# 03_Keys.net
KiCad netlist of a schematic drawn in Altium Designer
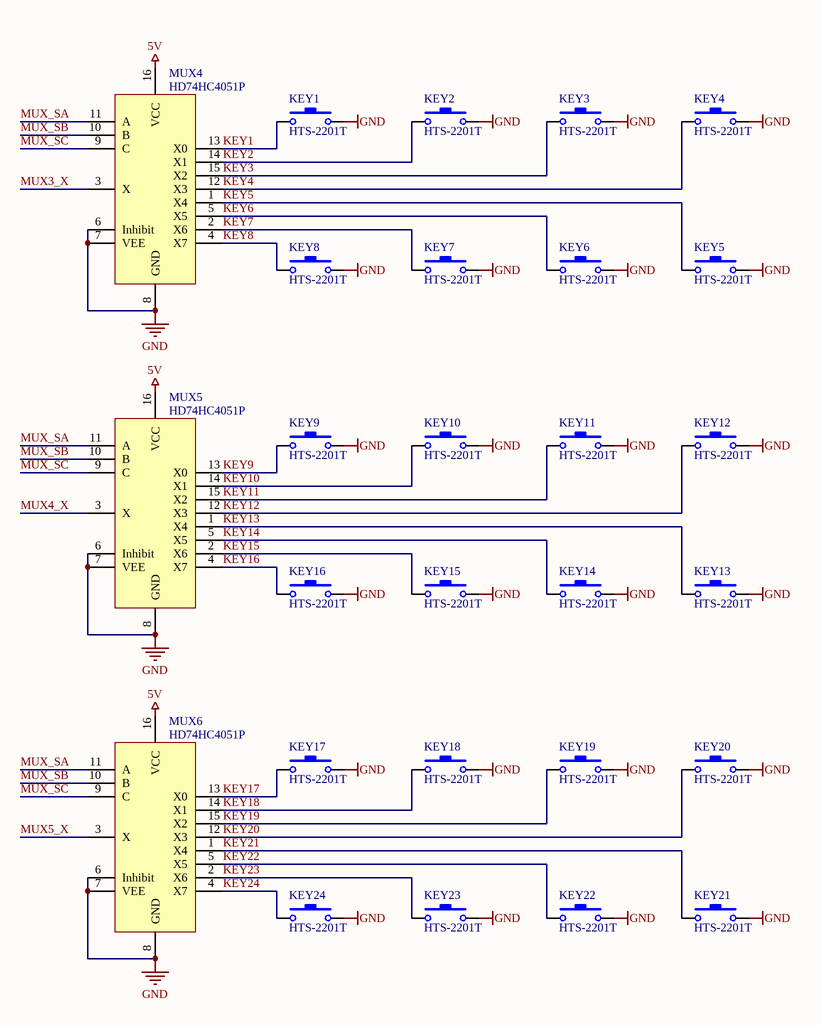
[diagram p0: 03.Keys.SchDoc]

(export (version "E")
  (design (tool "Eeschema 10.0.6"))
  (components
    (comp (ref "KEY1")
      (value "HTS-2201T")
      (footprint "ALPS-SKHC-12mm - NO SILK")
      (libsource (lib "Jixuan's library") (part "Tact Switch HTS-2201T"))
    )
    (comp (ref "KEY2")
      (value "HTS-2201T")
      (footprint "ALPS-SKHC-12mm - NO SILK")
      (libsource (lib "Jixuan's library") (part "Tact Switch HTS-2201T"))
    )
    (comp (ref "KEY3")
      (value "HTS-2201T")
      (footprint "ALPS-SKHC-12mm - NO SILK")
      (libsource (lib "Jixuan's library") (part "Tact Switch HTS-2201T"))
    )
    (comp (ref "KEY4")
      (value "HTS-2201T")
      (footprint "ALPS-SKHC-12mm - NO SILK")
      (libsource (lib "Jixuan's library") (part "Tact Switch HTS-2201T"))
    )
    (comp (ref "KEY5")
      (value "HTS-2201T")
      (footprint "ALPS-SKHC-12mm - NO SILK")
      (libsource (lib "Jixuan's library") (part "Tact Switch HTS-2201T"))
    )
    (comp (ref "KEY6")
      (value "HTS-2201T")
      (footprint "ALPS-SKHC-12mm - NO SILK")
      (libsource (lib "Jixuan's library") (part "Tact Switch HTS-2201T"))
    )
    (comp (ref "KEY7")
      (value "HTS-2201T")
      (footprint "ALPS-SKHC-12mm - NO SILK")
      (libsource (lib "Jixuan's library") (part "Tact Switch HTS-2201T"))
    )
    (comp (ref "KEY8")
      (value "HTS-2201T")
      (footprint "ALPS-SKHC-12mm - NO SILK")
      (libsource (lib "Jixuan's library") (part "Tact Switch HTS-2201T"))
    )
    (comp (ref "KEY9")
      (value "HTS-2201T")
      (footprint "ALPS-SKHC-12mm - NO SILK")
      (libsource (lib "Jixuan's library") (part "Tact Switch HTS-2201T"))
    )
    (comp (ref "KEY10")
      (value "HTS-2201T")
      (footprint "ALPS-SKHC-12mm - NO SILK")
      (libsource (lib "Jixuan's library") (part "Tact Switch HTS-2201T"))
    )
    (comp (ref "KEY11")
      (value "HTS-2201T")
      (footprint "ALPS-SKHC-12mm - NO SILK")
      (libsource (lib "Jixuan's library") (part "Tact Switch HTS-2201T"))
    )
    (comp (ref "KEY12")
      (value "HTS-2201T")
      (footprint "ALPS-SKHC-12mm - NO SILK")
      (libsource (lib "Jixuan's library") (part "Tact Switch HTS-2201T"))
    )
    (comp (ref "KEY13")
      (value "HTS-2201T")
      (footprint "ALPS-SKHC-12mm - NO SILK")
      (libsource (lib "Jixuan's library") (part "Tact Switch HTS-2201T"))
    )
    (comp (ref "KEY14")
      (value "HTS-2201T")
      (footprint "ALPS-SKHC-12mm - NO SILK")
      (libsource (lib "Jixuan's library") (part "Tact Switch HTS-2201T"))
    )
    (comp (ref "KEY15")
      (value "HTS-2201T")
      (footprint "ALPS-SKHC-12mm - NO SILK")
      (libsource (lib "Jixuan's library") (part "Tact Switch HTS-2201T"))
    )
    (comp (ref "KEY16")
      (value "HTS-2201T")
      (footprint "ALPS-SKHC-12mm - NO SILK")
      (libsource (lib "Jixuan's library") (part "Tact Switch HTS-2201T"))
    )
    (comp (ref "KEY17")
      (value "HTS-2201T")
      (footprint "ALPS-SKHC-12mm - NO SILK")
      (libsource (lib "Jixuan's library") (part "Tact Switch HTS-2201T"))
    )
    (comp (ref "KEY18")
      (value "HTS-2201T")
      (footprint "ALPS-SKHC-12mm - NO SILK")
      (libsource (lib "Jixuan's library") (part "Tact Switch HTS-2201T"))
    )
    (comp (ref "KEY19")
      (value "HTS-2201T")
      (footprint "ALPS-SKHC-12mm - NO SILK")
      (libsource (lib "Jixuan's library") (part "Tact Switch HTS-2201T"))
    )
    (comp (ref "KEY20")
      (value "HTS-2201T")
      (footprint "ALPS-SKHC-12mm - NO SILK")
      (libsource (lib "Jixuan's library") (part "Tact Switch HTS-2201T"))
    )
    (comp (ref "KEY21")
      (value "HTS-2201T")
      (footprint "ALPS-SKHC-12mm - NO SILK")
      (libsource (lib "Jixuan's library") (part "Tact Switch HTS-2201T"))
    )
    (comp (ref "KEY22")
      (value "HTS-2201T")
      (footprint "ALPS-SKHC-12mm - NO SILK")
      (libsource (lib "Jixuan's library") (part "Tact Switch HTS-2201T"))
    )
    (comp (ref "KEY23")
      (value "HTS-2201T")
      (footprint "ALPS-SKHC-12mm - NO SILK")
      (libsource (lib "Jixuan's library") (part "Tact Switch HTS-2201T"))
    )
    (comp (ref "KEY24")
      (value "HTS-2201T")
      (footprint "ALPS-SKHC-12mm - NO SILK")
      (libsource (lib "Jixuan's library") (part "Tact Switch HTS-2201T"))
    )
    (comp (ref "MUX4")
      (value "HD74HC4051P")
      (footprint "DIP-16")
      (libsource (lib "Jixuan's library") (part "TC74HC4051AF"))
    )
    (comp (ref "MUX5")
      (value "HD74HC4051P")
      (footprint "DIP-16")
      (libsource (lib "Jixuan's library") (part "TC74HC4051AF"))
    )
    (comp (ref "MUX6")
      (value "HD74HC4051P")
      (footprint "DIP-16")
      (libsource (lib "Jixuan's library") (part "TC74HC4051AF"))
    )
  )
  (nets
    (net (code "1") (name "/KEY1") (class "Default")
      (node (ref "KEY1") (pin "2") (pinfunction "2_2") (pintype "passive"))
      (node (ref "MUX4") (pin "13") (pinfunction "X0_13") (pintype "passive"))
    )
    (net (code "2") (name "/KEY2") (class "Default")
      (node (ref "KEY2") (pin "2") (pinfunction "2_2") (pintype "passive"))
      (node (ref "MUX4") (pin "14") (pinfunction "X1_14") (pintype "passive"))
    )
    (net (code "3") (name "/KEY3") (class "Default")
      (node (ref "KEY3") (pin "2") (pinfunction "2_2") (pintype "passive"))
      (node (ref "MUX4") (pin "15") (pinfunction "X2_15") (pintype "passive"))
    )
    (net (code "4") (name "/KEY4") (class "Default")
      (node (ref "KEY4") (pin "2") (pinfunction "2_2") (pintype "passive"))
      (node (ref "MUX4") (pin "12") (pinfunction "X3_12") (pintype "passive"))
    )
    (net (code "5") (name "/KEY5") (class "Default")
      (node (ref "KEY5") (pin "2") (pinfunction "2_2") (pintype "passive"))
      (node (ref "MUX4") (pin "1") (pinfunction "X4_1") (pintype "passive"))
    )
    (net (code "6") (name "/KEY6") (class "Default")
      (node (ref "KEY6") (pin "2") (pinfunction "2_2") (pintype "passive"))
      (node (ref "MUX4") (pin "5") (pinfunction "X5_5") (pintype "passive"))
    )
    (net (code "7") (name "/KEY7") (class "Default")
      (node (ref "KEY7") (pin "2") (pinfunction "2_2") (pintype "passive"))
      (node (ref "MUX4") (pin "2") (pinfunction "X6_2") (pintype "passive"))
    )
    (net (code "8") (name "/KEY8") (class "Default")
      (node (ref "KEY8") (pin "2") (pinfunction "2_2") (pintype "passive"))
      (node (ref "MUX4") (pin "4") (pinfunction "X7_4") (pintype "passive"))
    )
    (net (code "9") (name "/KEY9") (class "Default")
      (node (ref "KEY9") (pin "2") (pinfunction "2_2") (pintype "passive"))
      (node (ref "MUX5") (pin "13") (pinfunction "X0_13") (pintype "passive"))
    )
    (net (code "10") (name "/KEY10") (class "Default")
      (node (ref "KEY10") (pin "2") (pinfunction "2_2") (pintype "passive"))
      (node (ref "MUX5") (pin "14") (pinfunction "X1_14") (pintype "passive"))
    )
    (net (code "11") (name "/KEY11") (class "Default")
      (node (ref "KEY11") (pin "2") (pinfunction "2_2") (pintype "passive"))
      (node (ref "MUX5") (pin "15") (pinfunction "X2_15") (pintype "passive"))
    )
    (net (code "12") (name "/KEY12") (class "Default")
      (node (ref "KEY12") (pin "2") (pinfunction "2_2") (pintype "passive"))
      (node (ref "MUX5") (pin "12") (pinfunction "X3_12") (pintype "passive"))
    )
    (net (code "13") (name "/KEY13") (class "Default")
      (node (ref "KEY13") (pin "2") (pinfunction "2_2") (pintype "passive"))
      (node (ref "MUX5") (pin "1") (pinfunction "X4_1") (pintype "passive"))
    )
    (net (code "14") (name "/KEY14") (class "Default")
      (node (ref "KEY14") (pin "2") (pinfunction "2_2") (pintype "passive"))
      (node (ref "MUX5") (pin "5") (pinfunction "X5_5") (pintype "passive"))
    )
    (net (code "15") (name "/KEY15") (class "Default")
      (node (ref "KEY15") (pin "2") (pinfunction "2_2") (pintype "passive"))
      (node (ref "MUX5") (pin "2") (pinfunction "X6_2") (pintype "passive"))
    )
    (net (code "16") (name "/KEY16") (class "Default")
      (node (ref "KEY16") (pin "2") (pinfunction "2_2") (pintype "passive"))
      (node (ref "MUX5") (pin "4") (pinfunction "X7_4") (pintype "passive"))
    )
    (net (code "17") (name "/KEY17") (class "Default")
      (node (ref "KEY17") (pin "2") (pinfunction "2_2") (pintype "passive"))
      (node (ref "MUX6") (pin "13") (pinfunction "X0_13") (pintype "passive"))
    )
    (net (code "18") (name "/KEY18") (class "Default")
      (node (ref "KEY18") (pin "2") (pinfunction "2_2") (pintype "passive"))
      (node (ref "MUX6") (pin "14") (pinfunction "X1_14") (pintype "passive"))
    )
    (net (code "19") (name "/KEY19") (class "Default")
      (node (ref "KEY19") (pin "2") (pinfunction "2_2") (pintype "passive"))
      (node (ref "MUX6") (pin "15") (pinfunction "X2_15") (pintype "passive"))
    )
    (net (code "20") (name "/KEY20") (class "Default")
      (node (ref "KEY20") (pin "2") (pinfunction "2_2") (pintype "passive"))
      (node (ref "MUX6") (pin "12") (pinfunction "X3_12") (pintype "passive"))
    )
    (net (code "21") (name "/KEY21") (class "Default")
      (node (ref "KEY21") (pin "2") (pinfunction "2_2") (pintype "passive"))
      (node (ref "MUX6") (pin "1") (pinfunction "X4_1") (pintype "passive"))
    )
    (net (code "22") (name "/KEY22") (class "Default")
      (node (ref "KEY22") (pin "2") (pinfunction "2_2") (pintype "passive"))
      (node (ref "MUX6") (pin "5") (pinfunction "X5_5") (pintype "passive"))
    )
    (net (code "23") (name "/KEY23") (class "Default")
      (node (ref "KEY23") (pin "2") (pinfunction "2_2") (pintype "passive"))
      (node (ref "MUX6") (pin "2") (pinfunction "X6_2") (pintype "passive"))
    )
    (net (code "24") (name "/KEY24") (class "Default")
      (node (ref "KEY24") (pin "2") (pinfunction "2_2") (pintype "passive"))
      (node (ref "MUX6") (pin "4") (pinfunction "X7_4") (pintype "passive"))
    )
    (net (code "25") (name "/MUX3_X") (class "Default")
      (node (ref "MUX4") (pin "3") (pinfunction "X_3") (pintype "passive"))
    )
    (net (code "26") (name "/MUX4_X") (class "Default")
      (node (ref "MUX5") (pin "3") (pinfunction "X_3") (pintype "passive"))
    )
    (net (code "27") (name "/MUX5_X") (class "Default")
      (node (ref "MUX6") (pin "3") (pinfunction "X_3") (pintype "passive"))
    )
    (net (code "28") (name "/MUX_SA") (class "Default")
      (node (ref "MUX4") (pin "11") (pinfunction "A_11") (pintype "passive"))
      (node (ref "MUX5") (pin "11") (pinfunction "A_11") (pintype "passive"))
      (node (ref "MUX6") (pin "11") (pinfunction "A_11") (pintype "passive"))
    )
    (net (code "29") (name "/MUX_SB") (class "Default")
      (node (ref "MUX4") (pin "10") (pinfunction "B_10") (pintype "passive"))
      (node (ref "MUX5") (pin "10") (pinfunction "B_10") (pintype "passive"))
      (node (ref "MUX6") (pin "10") (pinfunction "B_10") (pintype "passive"))
    )
    (net (code "30") (name "/MUX_SC") (class "Default")
      (node (ref "MUX4") (pin "9") (pinfunction "C_9") (pintype "passive"))
      (node (ref "MUX5") (pin "9") (pinfunction "C_9") (pintype "passive"))
      (node (ref "MUX6") (pin "9") (pinfunction "C_9") (pintype "passive"))
    )
    (net (code "31") (name "5V") (class "Default")
      (node (ref "MUX4") (pin "16") (pinfunction "VCC_16") (pintype "passive"))
      (node (ref "MUX5") (pin "16") (pinfunction "VCC_16") (pintype "passive"))
      (node (ref "MUX6") (pin "16") (pinfunction "VCC_16") (pintype "passive"))
    )
    (net (code "32") (name "GND") (class "Default")
      (node (ref "KEY1") (pin "1") (pinfunction "1_1") (pintype "passive"))
      (node (ref "KEY10") (pin "1") (pinfunction "1_1") (pintype "passive"))
      (node (ref "KEY11") (pin "1") (pinfunction "1_1") (pintype "passive"))
      (node (ref "KEY12") (pin "1") (pinfunction "1_1") (pintype "passive"))
      (node (ref "KEY13") (pin "1") (pinfunction "1_1") (pintype "passive"))
      (node (ref "KEY14") (pin "1") (pinfunction "1_1") (pintype "passive"))
      (node (ref "KEY15") (pin "1") (pinfunction "1_1") (pintype "passive"))
      (node (ref "KEY16") (pin "1") (pinfunction "1_1") (pintype "passive"))
      (node (ref "KEY17") (pin "1") (pinfunction "1_1") (pintype "passive"))
      (node (ref "KEY18") (pin "1") (pinfunction "1_1") (pintype "passive"))
      (node (ref "KEY19") (pin "1") (pinfunction "1_1") (pintype "passive"))
      (node (ref "KEY2") (pin "1") (pinfunction "1_1") (pintype "passive"))
      (node (ref "KEY20") (pin "1") (pinfunction "1_1") (pintype "passive"))
      (node (ref "KEY21") (pin "1") (pinfunction "1_1") (pintype "passive"))
      (node (ref "KEY22") (pin "1") (pinfunction "1_1") (pintype "passive"))
      (node (ref "KEY23") (pin "1") (pinfunction "1_1") (pintype "passive"))
      (node (ref "KEY24") (pin "1") (pinfunction "1_1") (pintype "passive"))
      (node (ref "KEY3") (pin "1") (pinfunction "1_1") (pintype "passive"))
      (node (ref "KEY4") (pin "1") (pinfunction "1_1") (pintype "passive"))
      (node (ref "KEY5") (pin "1") (pinfunction "1_1") (pintype "passive"))
      (node (ref "KEY6") (pin "1") (pinfunction "1_1") (pintype "passive"))
      (node (ref "KEY7") (pin "1") (pinfunction "1_1") (pintype "passive"))
      (node (ref "KEY8") (pin "1") (pinfunction "1_1") (pintype "passive"))
      (node (ref "KEY9") (pin "1") (pinfunction "1_1") (pintype "passive"))
      (node (ref "MUX4") (pin "6") (pinfunction "Inhibit_6") (pintype "passive"))
      (node (ref "MUX4") (pin "7") (pinfunction "VEE_7") (pintype "passive"))
      (node (ref "MUX4") (pin "8") (pinfunction "GND_8") (pintype "passive"))
      (node (ref "MUX5") (pin "6") (pinfunction "Inhibit_6") (pintype "passive"))
      (node (ref "MUX5") (pin "7") (pinfunction "VEE_7") (pintype "passive"))
      (node (ref "MUX5") (pin "8") (pinfunction "GND_8") (pintype "passive"))
      (node (ref "MUX6") (pin "6") (pinfunction "Inhibit_6") (pintype "passive"))
      (node (ref "MUX6") (pin "7") (pinfunction "VEE_7") (pintype "passive"))
      (node (ref "MUX6") (pin "8") (pinfunction "GND_8") (pintype "passive"))
    )
  )
)
